# soundpuddle_linedriver_mk1.net
KiCad netlist of a schematic drawn in EAGLE
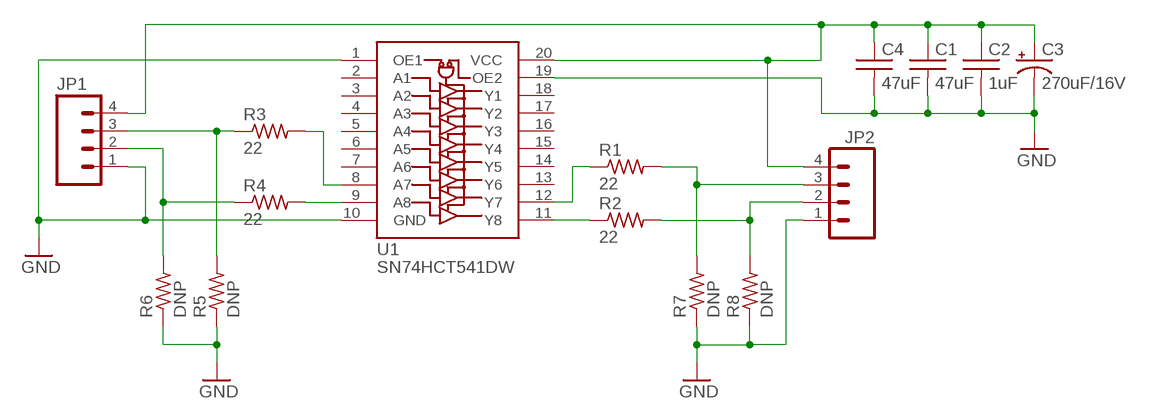
[diagram p0: schematic, sheet 1]

(export (version "E")
  (design (tool "Eeschema 10.0.6"))
  (components
    (comp (ref "C1")
      (value "47uF")
      (footprint "eagle-import:1206")
      (libsource (lib "eagle-import") (part "CAPACITORC_1206"))
    )
    (comp (ref "C2")
      (value "1uF")
      (footprint "eagle-import:0603")
      (libsource (lib "eagle-import") (part "CAPACITORC_0603"))
    )
    (comp (ref "C3")
      (value "270uF/16V")
      (footprint "eagle-import:CAP_RADIAL_THRUHOLE_8MM_DIA")
      (libsource (lib "eagle-import") (part "CAPACITOR_ELEC8MM_DIA"))
    )
    (comp (ref "C4")
      (value "47uF")
      (footprint "eagle-import:1206")
      (libsource (lib "eagle-import") (part "CAPACITORC_1206"))
    )
    (comp (ref "JP1")
      (value "M04POLAR")
      (footprint "eagle-import:MOLEX-1X4")
      (libsource (lib "eagle-import") (part "M04POLAR"))
    )
    (comp (ref "JP2")
      (value "M04POLAR")
      (footprint "eagle-import:MOLEX-1X4")
      (libsource (lib "eagle-import") (part "M04POLAR"))
    )
    (comp (ref "R1")
      (value "22")
      (footprint "eagle-import:0805")
      (libsource (lib "eagle-import") (part "RESISTORR_0805"))
    )
    (comp (ref "R2")
      (value "22")
      (footprint "eagle-import:0805")
      (libsource (lib "eagle-import") (part "RESISTORR_0805"))
    )
    (comp (ref "R3")
      (value "22")
      (footprint "eagle-import:0805")
      (libsource (lib "eagle-import") (part "RESISTORR_0805"))
    )
    (comp (ref "R4")
      (value "22")
      (footprint "eagle-import:0805")
      (libsource (lib "eagle-import") (part "RESISTORR_0805"))
    )
    (comp (ref "R5")
      (value "DNP")
      (footprint "eagle-import:0805")
      (libsource (lib "eagle-import") (part "RESISTORR_0805"))
    )
    (comp (ref "R6")
      (value "DNP")
      (footprint "eagle-import:0805")
      (libsource (lib "eagle-import") (part "RESISTORR_0805"))
    )
    (comp (ref "R7")
      (value "DNP")
      (footprint "eagle-import:0805")
      (libsource (lib "eagle-import") (part "RESISTORR_0805"))
    )
    (comp (ref "R8")
      (value "DNP")
      (footprint "eagle-import:0805")
      (libsource (lib "eagle-import") (part "RESISTORR_0805"))
    )
    (comp (ref "U1")
      (value "SN74HCT541DW")
      (footprint "eagle-import:SOIC-20_TI_DW")
      (libsource (lib "eagle-import") (part "SN74HCT541DW"))
    )
  )
  (nets
    (net (code "1") (name "GND") (class "Default")
      (node (ref "C1") (pin "P$2") (pinfunction "2_P$2") (pintype "passive"))
      (node (ref "C2") (pin "2") (pinfunction "2_2") (pintype "passive"))
      (node (ref "C3") (pin "P$1") (pinfunction "-_P$1") (pintype "passive"))
      (node (ref "C4") (pin "P$2") (pinfunction "2_P$2") (pintype "passive"))
      (node (ref "JP1") (pin "1") (pinfunction "1_1") (pintype "passive"))
      (node (ref "JP2") (pin "1") (pinfunction "1_1") (pintype "passive"))
      (node (ref "R5") (pin "1") (pinfunction "1_1") (pintype "passive"))
      (node (ref "R6") (pin "1") (pinfunction "1_1") (pintype "passive"))
      (node (ref "R7") (pin "1") (pinfunction "1_1") (pintype "passive"))
      (node (ref "R8") (pin "1") (pinfunction "1_1") (pintype "passive"))
      (node (ref "U1") (pin "1") (pinfunction "OE1_1") (pintype "bidirectional"))
      (node (ref "U1") (pin "10") (pinfunction "GND_10") (pintype "bidirectional"))
      (node (ref "U1") (pin "19") (pinfunction "OE2_19") (pintype "bidirectional"))
    )
    (net (code "2") (name "Net-(C1-1)") (class "Default")
      (node (ref "C1") (pin "P$1") (pinfunction "1_P$1") (pintype "passive"))
      (node (ref "C2") (pin "1") (pinfunction "1_1") (pintype "passive"))
      (node (ref "C3") (pin "P$2") (pinfunction "+_P$2") (pintype "passive"))
      (node (ref "C4") (pin "P$1") (pinfunction "1_P$1") (pintype "passive"))
      (node (ref "JP1") (pin "4") (pinfunction "4_4") (pintype "passive"))
      (node (ref "JP2") (pin "4") (pinfunction "4_4") (pintype "passive"))
      (node (ref "U1") (pin "20") (pinfunction "VCC_20") (pintype "bidirectional"))
    )
    (net (code "3") (name "Net-(JP1-Pad2)") (class "Default")
      (node (ref "JP1") (pin "2") (pinfunction "2_2") (pintype "passive"))
      (node (ref "R4") (pin "1") (pinfunction "1_1") (pintype "passive"))
      (node (ref "R6") (pin "2") (pinfunction "2_2") (pintype "passive"))
    )
    (net (code "4") (name "Net-(JP1-Pad3)") (class "Default")
      (node (ref "JP1") (pin "3") (pinfunction "3_3") (pintype "passive"))
      (node (ref "R3") (pin "1") (pinfunction "1_1") (pintype "passive"))
      (node (ref "R5") (pin "2") (pinfunction "2_2") (pintype "passive"))
    )
    (net (code "5") (name "Net-(JP2-Pad2)") (class "Default")
      (node (ref "JP2") (pin "2") (pinfunction "2_2") (pintype "passive"))
      (node (ref "R2") (pin "2") (pinfunction "2_2") (pintype "passive"))
      (node (ref "R8") (pin "2") (pinfunction "2_2") (pintype "passive"))
    )
    (net (code "6") (name "Net-(JP2-Pad3)") (class "Default")
      (node (ref "JP2") (pin "3") (pinfunction "3_3") (pintype "passive"))
      (node (ref "R1") (pin "2") (pinfunction "2_2") (pintype "passive"))
      (node (ref "R7") (pin "2") (pinfunction "2_2") (pintype "passive"))
    )
    (net (code "7") (name "Net-(U1-A7)") (class "Default")
      (node (ref "R3") (pin "2") (pinfunction "2_2") (pintype "passive"))
      (node (ref "U1") (pin "8") (pinfunction "A7_8") (pintype "bidirectional"))
    )
    (net (code "8") (name "Net-(U1-A8)") (class "Default")
      (node (ref "R4") (pin "2") (pinfunction "2_2") (pintype "passive"))
      (node (ref "U1") (pin "9") (pinfunction "A8_9") (pintype "bidirectional"))
    )
    (net (code "9") (name "Net-(U1-Y7)") (class "Default")
      (node (ref "R1") (pin "1") (pinfunction "1_1") (pintype "passive"))
      (node (ref "U1") (pin "12") (pinfunction "Y7_12") (pintype "bidirectional"))
    )
    (net (code "10") (name "Net-(U1-Y8)") (class "Default")
      (node (ref "R2") (pin "1") (pinfunction "1_1") (pintype "passive"))
      (node (ref "U1") (pin "11") (pinfunction "Y8_11") (pintype "bidirectional"))
    )
    (net (code "11") (name "unconnected-(U1-A1-Pad2)") (class "Default")
      (node (ref "U1") (pin "2") (pinfunction "A1_2") (pintype "bidirectional"))
    )
    (net (code "12") (name "unconnected-(U1-A2-Pad3)") (class "Default")
      (node (ref "U1") (pin "3") (pinfunction "A2_3") (pintype "bidirectional"))
    )
    (net (code "13") (name "unconnected-(U1-A3-Pad4)") (class "Default")
      (node (ref "U1") (pin "4") (pinfunction "A3_4") (pintype "bidirectional"))
    )
    (net (code "14") (name "unconnected-(U1-A4-Pad5)") (class "Default")
      (node (ref "U1") (pin "5") (pinfunction "A4_5") (pintype "bidirectional"))
    )
    (net (code "15") (name "unconnected-(U1-A5-Pad6)") (class "Default")
      (node (ref "U1") (pin "6") (pinfunction "A5_6") (pintype "bidirectional"))
    )
    (net (code "16") (name "unconnected-(U1-A6-Pad7)") (class "Default")
      (node (ref "U1") (pin "7") (pinfunction "A6_7") (pintype "bidirectional"))
    )
    (net (code "17") (name "unconnected-(U1-Y1-Pad18)") (class "Default")
      (node (ref "U1") (pin "18") (pinfunction "Y1_18") (pintype "bidirectional"))
    )
    (net (code "18") (name "unconnected-(U1-Y2-Pad17)") (class "Default")
      (node (ref "U1") (pin "17") (pinfunction "Y2_17") (pintype "bidirectional"))
    )
    (net (code "19") (name "unconnected-(U1-Y3-Pad16)") (class "Default")
      (node (ref "U1") (pin "16") (pinfunction "Y3_16") (pintype "bidirectional"))
    )
    (net (code "20") (name "unconnected-(U1-Y4-Pad15)") (class "Default")
      (node (ref "U1") (pin "15") (pinfunction "Y4_15") (pintype "bidirectional"))
    )
    (net (code "21") (name "unconnected-(U1-Y5-Pad14)") (class "Default")
      (node (ref "U1") (pin "14") (pinfunction "Y5_14") (pintype "bidirectional"))
    )
    (net (code "22") (name "unconnected-(U1-Y6-Pad13)") (class "Default")
      (node (ref "U1") (pin "13") (pinfunction "Y6_13") (pintype "bidirectional"))
    )
  )
)
